# PowCarbinBoard_FPGA.net
KiCad netlist of a schematic drawn in Altium Designer
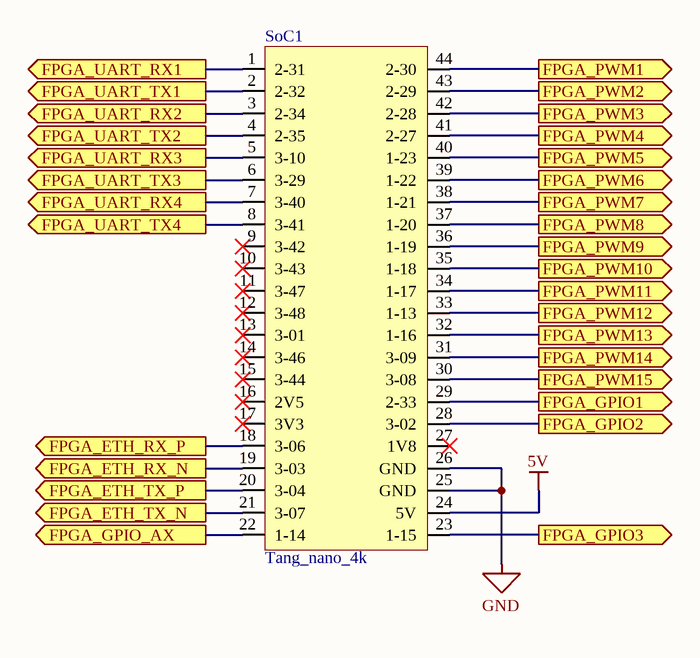
[diagram p0: PowCarbinBoard_FPGA.SchDoc]

(export (version "E")
  (design (tool "Eeschema 10.0.6"))
  (components
    (comp (ref "SoC1")
      (value "Tang_nano_4k")
      (footprint "SIPEED-TANG_nano_4k")
      (libsource (lib "MySchLib") (part "SIPEED-TANG_nano_4k"))
    )
  )
  (nets
    (net (code "1") (name "/FPGA_ETH_RX_N") (class "Default")
      (node (ref "SoC1") (pin "19") (pinfunction "3-03_19") (pintype "passive"))
    )
    (net (code "2") (name "/FPGA_ETH_RX_P") (class "Default")
      (node (ref "SoC1") (pin "18") (pinfunction "3-06_18") (pintype "passive"))
    )
    (net (code "3") (name "/FPGA_ETH_TX_N") (class "Default")
      (node (ref "SoC1") (pin "21") (pinfunction "3-07_21") (pintype "passive"))
    )
    (net (code "4") (name "/FPGA_ETH_TX_P") (class "Default")
      (node (ref "SoC1") (pin "20") (pinfunction "3-04_20") (pintype "passive"))
    )
    (net (code "5") (name "/FPGA_GPIO1") (class "Default")
      (node (ref "SoC1") (pin "29") (pinfunction "2-33_29") (pintype "passive"))
    )
    (net (code "6") (name "/FPGA_GPIO2") (class "Default")
      (node (ref "SoC1") (pin "28") (pinfunction "3-02_28") (pintype "passive"))
    )
    (net (code "7") (name "/FPGA_GPIO3") (class "Default")
      (node (ref "SoC1") (pin "23") (pinfunction "1-15_23") (pintype "passive"))
    )
    (net (code "8") (name "/FPGA_GPIO_AX") (class "Default")
      (node (ref "SoC1") (pin "22") (pinfunction "1-14_22") (pintype "passive"))
    )
    (net (code "9") (name "/FPGA_PWM1") (class "Default")
      (node (ref "SoC1") (pin "44") (pinfunction "2-30_44") (pintype "passive"))
    )
    (net (code "10") (name "/FPGA_PWM2") (class "Default")
      (node (ref "SoC1") (pin "43") (pinfunction "2-29_43") (pintype "passive"))
    )
    (net (code "11") (name "/FPGA_PWM3") (class "Default")
      (node (ref "SoC1") (pin "42") (pinfunction "2-28_42") (pintype "passive"))
    )
    (net (code "12") (name "/FPGA_PWM4") (class "Default")
      (node (ref "SoC1") (pin "41") (pinfunction "2-27_41") (pintype "passive"))
    )
    (net (code "13") (name "/FPGA_PWM5") (class "Default")
      (node (ref "SoC1") (pin "40") (pinfunction "1-23_40") (pintype "passive"))
    )
    (net (code "14") (name "/FPGA_PWM6") (class "Default")
      (node (ref "SoC1") (pin "39") (pinfunction "1-22_39") (pintype "passive"))
    )
    (net (code "15") (name "/FPGA_PWM7") (class "Default")
      (node (ref "SoC1") (pin "38") (pinfunction "1-21_38") (pintype "passive"))
    )
    (net (code "16") (name "/FPGA_PWM8") (class "Default")
      (node (ref "SoC1") (pin "37") (pinfunction "1-20_37") (pintype "passive"))
    )
    (net (code "17") (name "/FPGA_PWM9") (class "Default")
      (node (ref "SoC1") (pin "36") (pinfunction "1-19_36") (pintype "passive"))
    )
    (net (code "18") (name "/FPGA_PWM10") (class "Default")
      (node (ref "SoC1") (pin "35") (pinfunction "1-18_35") (pintype "passive"))
    )
    (net (code "19") (name "/FPGA_PWM11") (class "Default")
      (node (ref "SoC1") (pin "34") (pinfunction "1-17_34") (pintype "passive"))
    )
    (net (code "20") (name "/FPGA_PWM12") (class "Default")
      (node (ref "SoC1") (pin "33") (pinfunction "1-13_33") (pintype "passive"))
    )
    (net (code "21") (name "/FPGA_PWM13") (class "Default")
      (node (ref "SoC1") (pin "32") (pinfunction "1-16_32") (pintype "passive"))
    )
    (net (code "22") (name "/FPGA_PWM14") (class "Default")
      (node (ref "SoC1") (pin "31") (pinfunction "3-09_31") (pintype "passive"))
    )
    (net (code "23") (name "/FPGA_PWM15") (class "Default")
      (node (ref "SoC1") (pin "30") (pinfunction "3-08_30") (pintype "passive"))
    )
    (net (code "24") (name "/FPGA_UART_RX1") (class "Default")
      (node (ref "SoC1") (pin "1") (pinfunction "2-31_1") (pintype "passive"))
    )
    (net (code "25") (name "/FPGA_UART_RX2") (class "Default")
      (node (ref "SoC1") (pin "3") (pinfunction "2-34_3") (pintype "passive"))
    )
    (net (code "26") (name "/FPGA_UART_RX3") (class "Default")
      (node (ref "SoC1") (pin "5") (pinfunction "3-10_5") (pintype "passive"))
    )
    (net (code "27") (name "/FPGA_UART_RX4") (class "Default")
      (node (ref "SoC1") (pin "7") (pinfunction "3-40_7") (pintype "passive"))
    )
    (net (code "28") (name "/FPGA_UART_TX1") (class "Default")
      (node (ref "SoC1") (pin "2") (pinfunction "2-32_2") (pintype "passive"))
    )
    (net (code "29") (name "/FPGA_UART_TX2") (class "Default")
      (node (ref "SoC1") (pin "4") (pinfunction "2-35_4") (pintype "passive"))
    )
    (net (code "30") (name "/FPGA_UART_TX3") (class "Default")
      (node (ref "SoC1") (pin "6") (pinfunction "3-29_6") (pintype "passive"))
    )
    (net (code "31") (name "/FPGA_UART_TX4") (class "Default")
      (node (ref "SoC1") (pin "8") (pinfunction "3-41_8") (pintype "passive"))
    )
    (net (code "32") (name "5V") (class "Default")
      (node (ref "SoC1") (pin "24") (pinfunction "5V_24") (pintype "passive"))
    )
    (net (code "33") (name "GND") (class "Default")
      (node (ref "SoC1") (pin "25") (pinfunction "GND_25") (pintype "passive"))
      (node (ref "SoC1") (pin "26") (pinfunction "GND_26") (pintype "passive"))
    )
    (net (code "34") (name "unconnected-(SoC1-1V8-Pad27)") (class "Default")
      (node (ref "SoC1") (pin "27") (pinfunction "1V8_27") (pintype "passive+no_connect"))
    )
    (net (code "35") (name "unconnected-(SoC1-2V5-Pad16)") (class "Default")
      (node (ref "SoC1") (pin "16") (pinfunction "2V5_16") (pintype "passive+no_connect"))
    )
    (net (code "36") (name "unconnected-(SoC1-3-01-Pad13)") (class "Default")
      (node (ref "SoC1") (pin "13") (pinfunction "3-01_13") (pintype "passive+no_connect"))
    )
    (net (code "37") (name "unconnected-(SoC1-3-42-Pad9)") (class "Default")
      (node (ref "SoC1") (pin "9") (pinfunction "3-42_9") (pintype "passive+no_connect"))
    )
    (net (code "38") (name "unconnected-(SoC1-3-43-Pad10)") (class "Default")
      (node (ref "SoC1") (pin "10") (pinfunction "3-43_10") (pintype "passive+no_connect"))
    )
    (net (code "39") (name "unconnected-(SoC1-3-44-Pad15)") (class "Default")
      (node (ref "SoC1") (pin "15") (pinfunction "3-44_15") (pintype "passive+no_connect"))
    )
    (net (code "40") (name "unconnected-(SoC1-3-46-Pad14)") (class "Default")
      (node (ref "SoC1") (pin "14") (pinfunction "3-46_14") (pintype "passive+no_connect"))
    )
    (net (code "41") (name "unconnected-(SoC1-3-47-Pad11)") (class "Default")
      (node (ref "SoC1") (pin "11") (pinfunction "3-47_11") (pintype "passive+no_connect"))
    )
    (net (code "42") (name "unconnected-(SoC1-3-48-Pad12)") (class "Default")
      (node (ref "SoC1") (pin "12") (pinfunction "3-48_12") (pintype "passive+no_connect"))
    )
    (net (code "43") (name "unconnected-(SoC1-3V3-Pad17)") (class "Default")
      (node (ref "SoC1") (pin "17") (pinfunction "3V3_17") (pintype "passive+no_connect"))
    )
  )
)
